# as3320-24BP.net
KiCad netlist of a schematic drawn in EAGLE
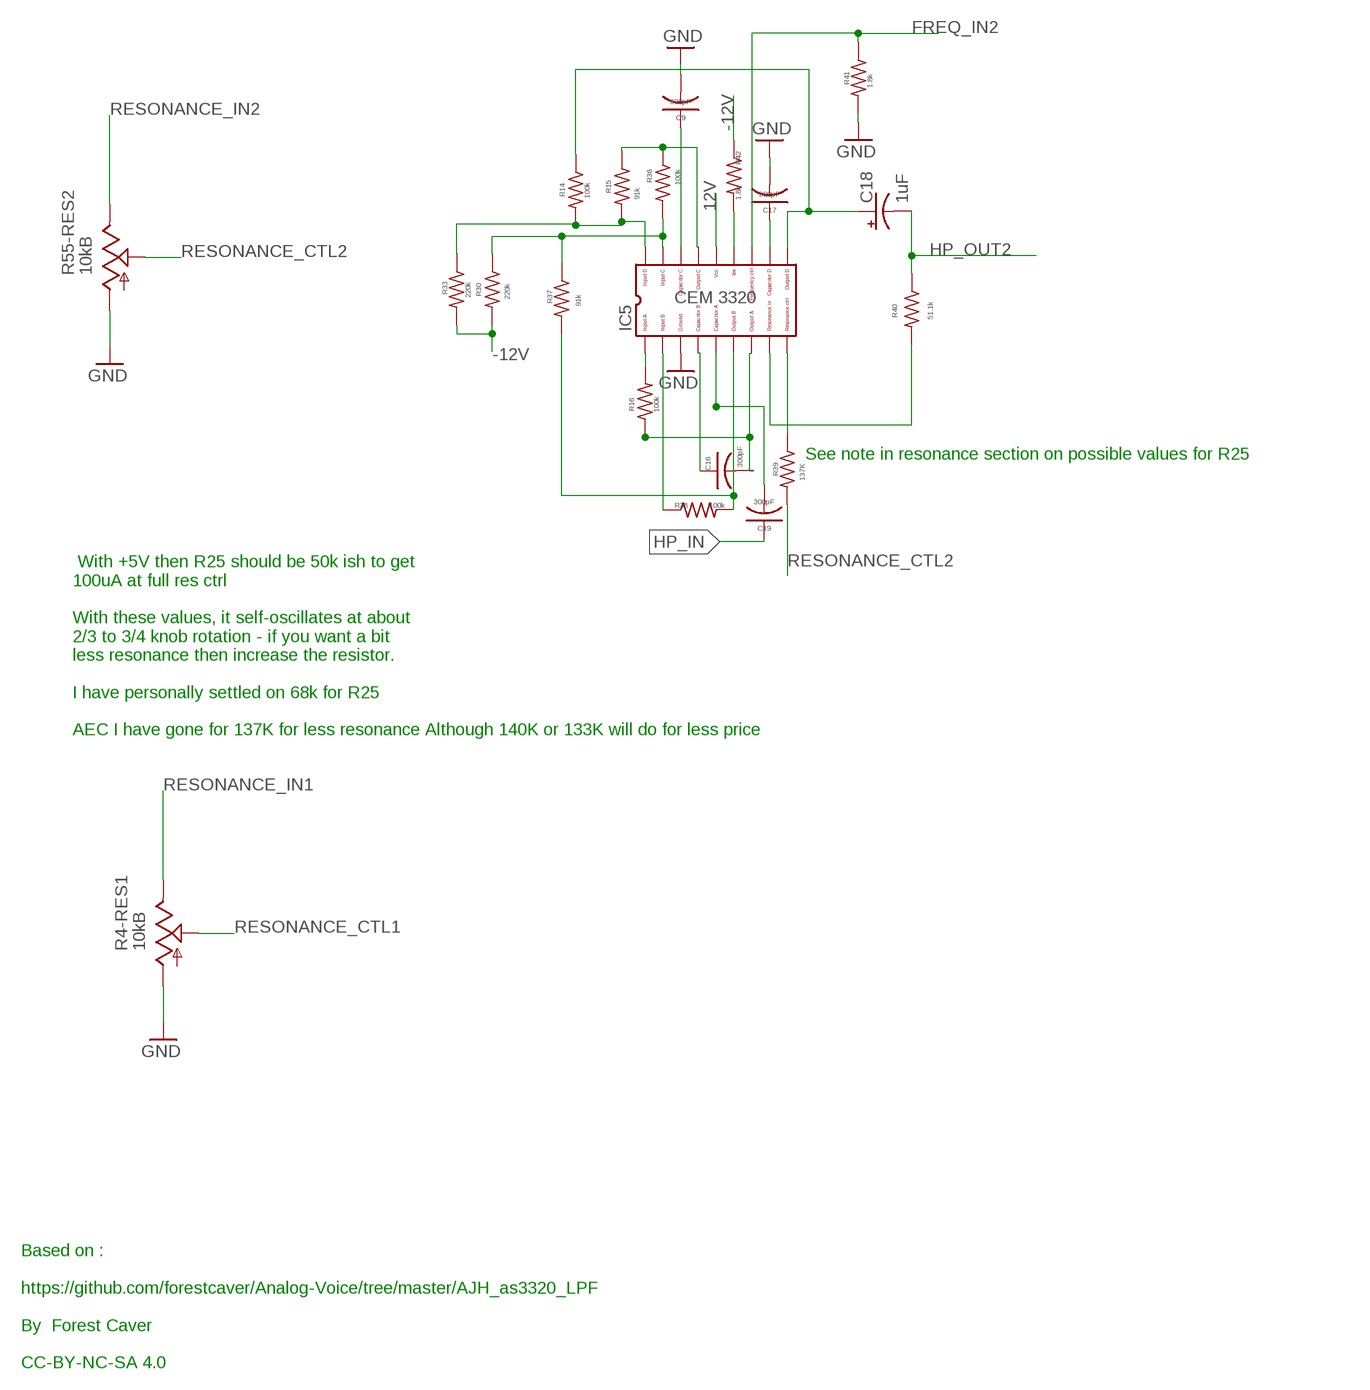
[diagram p0: schematic, sheet 1]
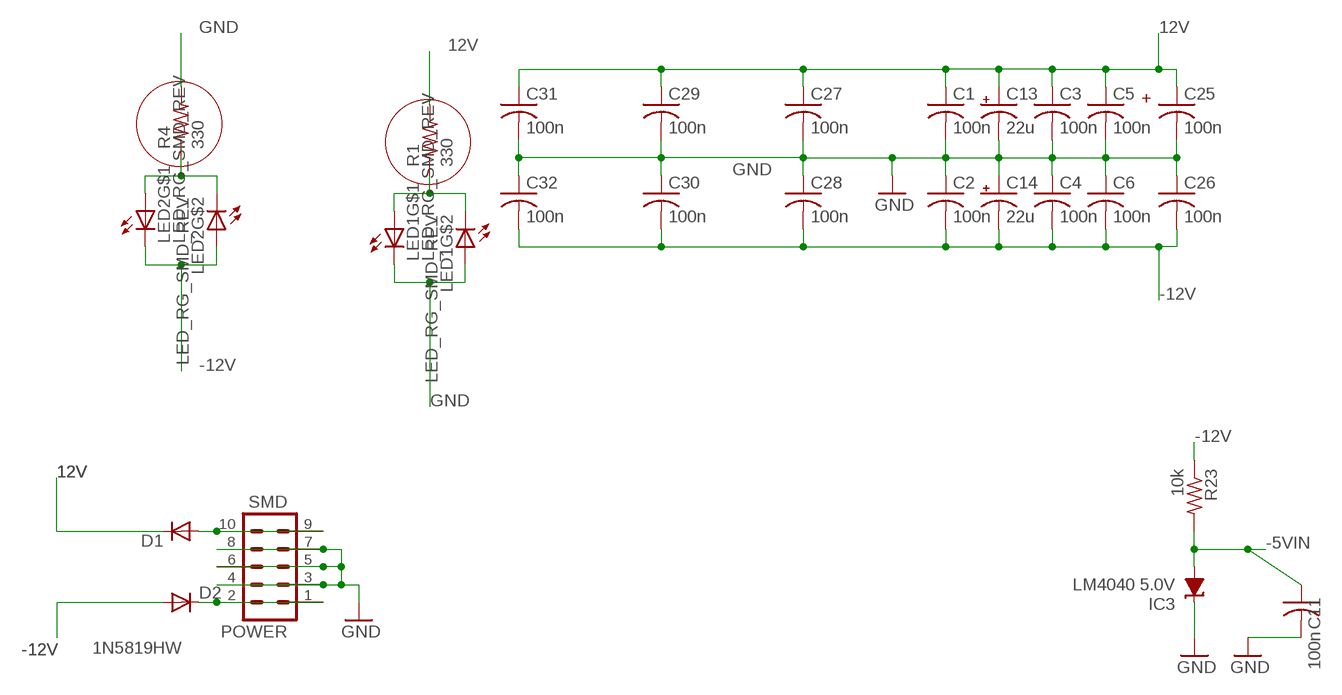
[diagram p1: schematic, sheet 2]
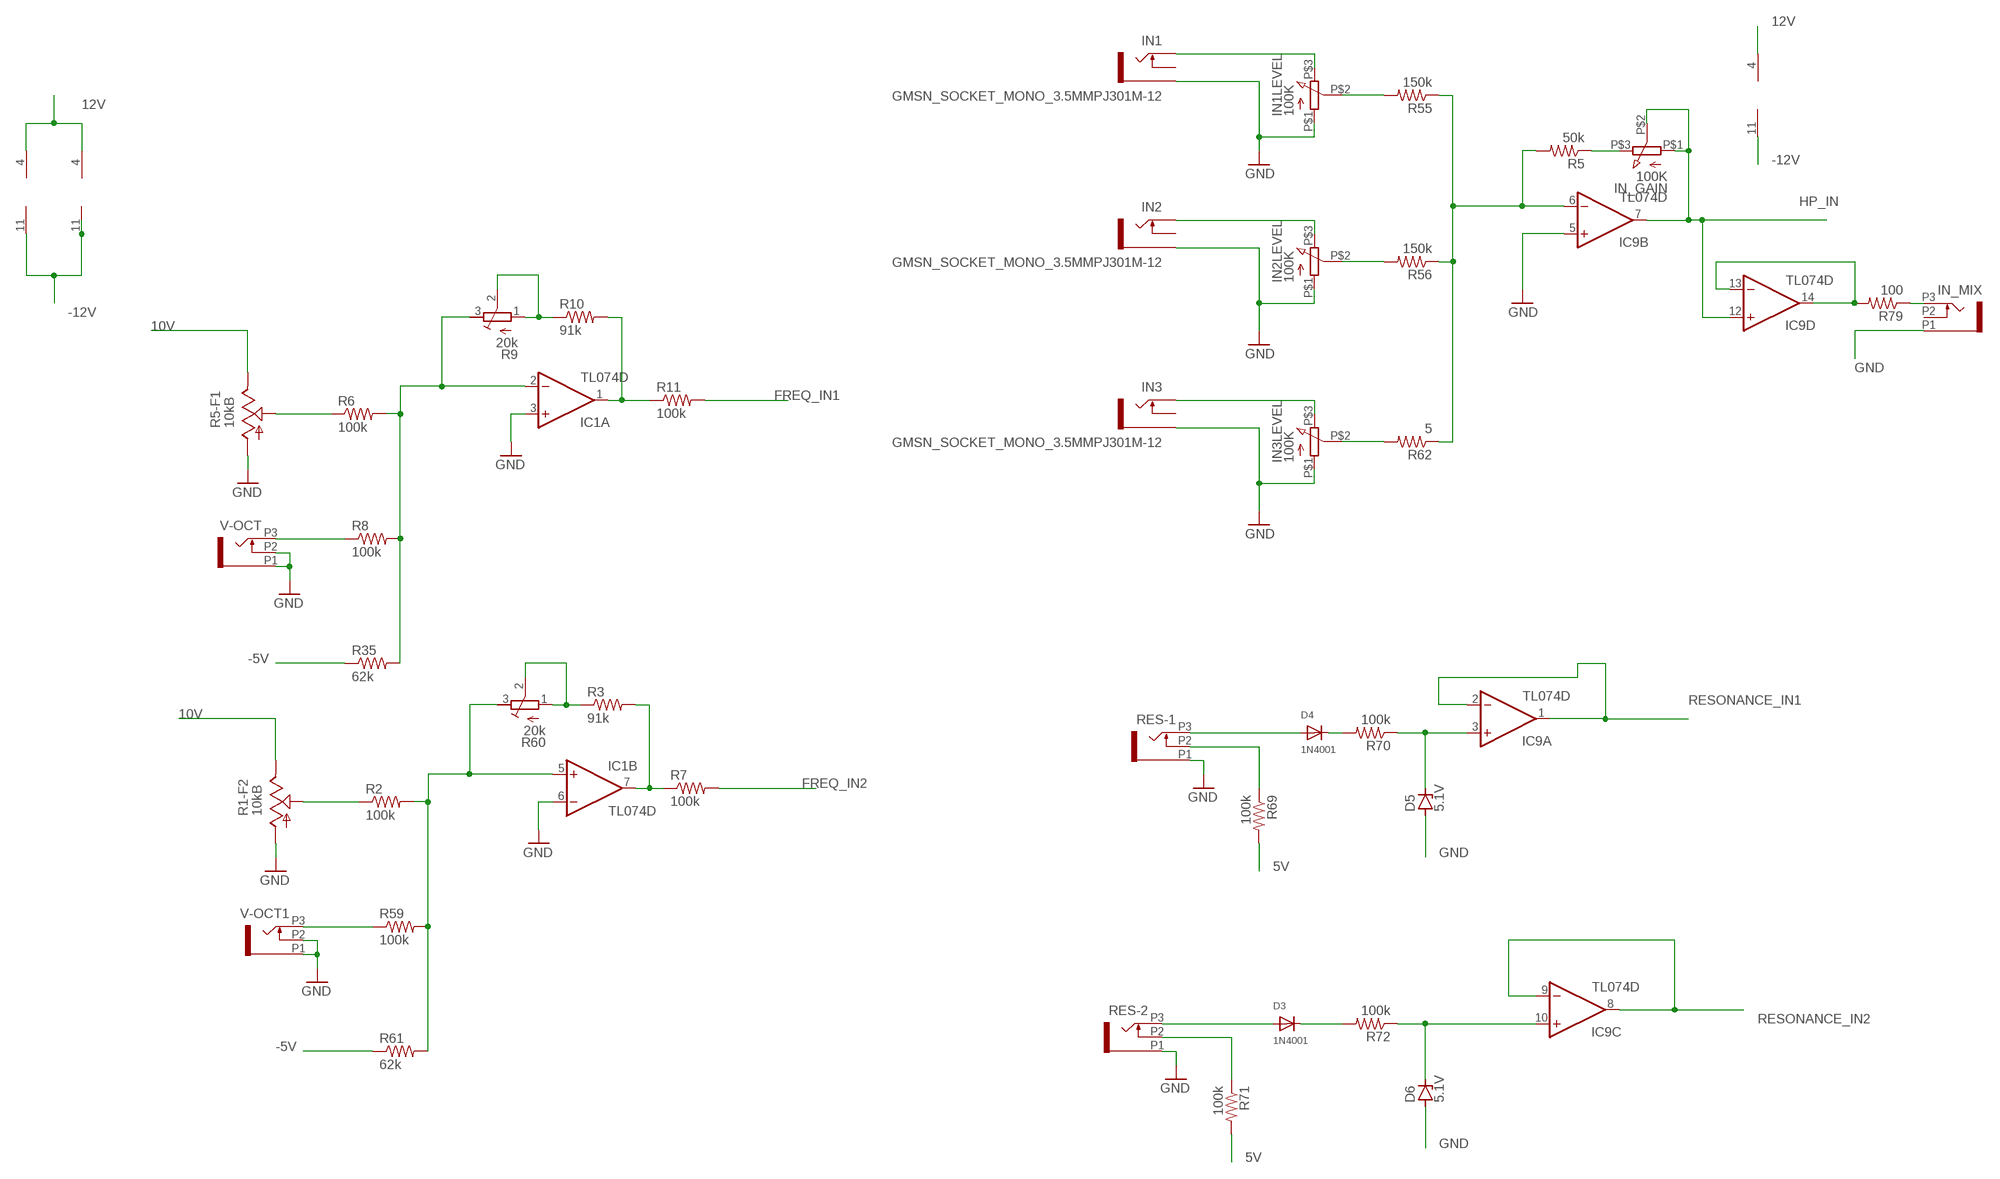
[diagram p2: schematic, sheet 3]
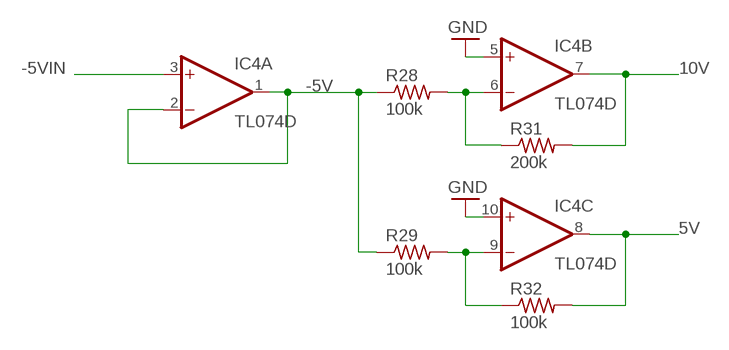
[diagram p3: schematic, sheet 4]
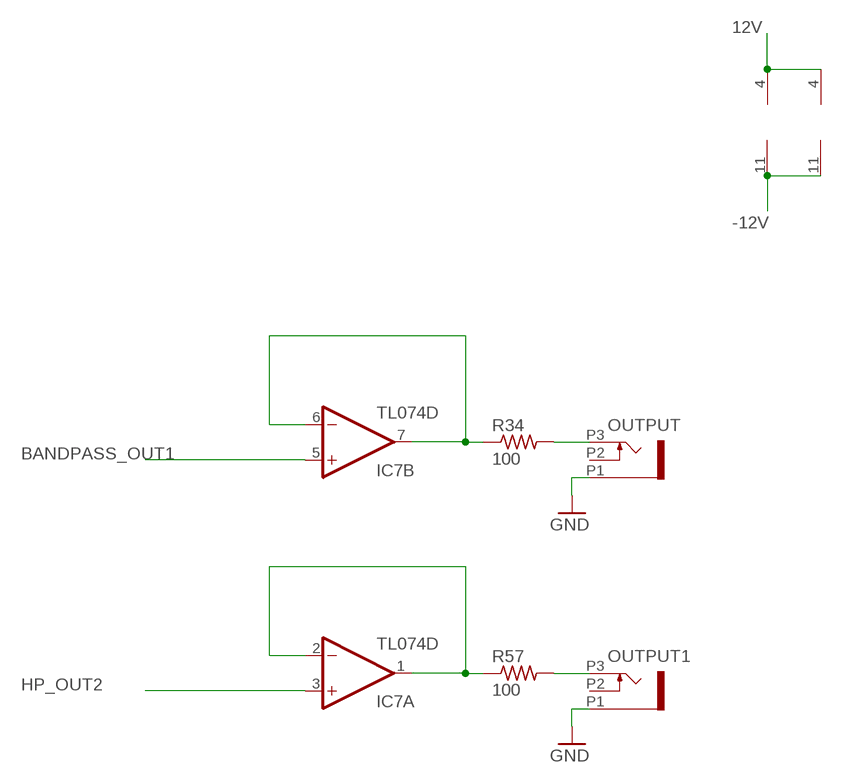
[diagram p4: schematic, sheet 5]

(export (version "E")
  (design (tool "Eeschema 10.0.6"))
  (components
    (comp (ref "D3")
      (value "1N4001")
      (footprint "eagle-import:SMADIODE")
      (libsource (lib "eagle-import") (part "DIODESMA"))
    )
    (comp (ref "D4")
      (value "1N4001")
      (footprint "eagle-import:SMADIODE")
      (libsource (lib "eagle-import") (part "DIODESMA"))
    )
    (comp (ref "D5")
      (value "5.1V")
      (footprint "eagle-import:SOT23")
      (fields (field (name "RS-PART") "816-7962"))
      (libsource (lib "eagle-import") (part "ZENER-DIODESOT23"))
    )
    (comp (ref "D6")
      (value "5.1V")
      (footprint "eagle-import:SOT23")
      (fields (field (name "RS-PART") "816-7962"))
      (libsource (lib "eagle-import") (part "ZENER-DIODESOT23"))
    )
    (comp (ref "IC1")
      (value "TL074D")
      (footprint "eagle-import:SO14")
      (libsource (lib "eagle-import") (part "linear_262_TL074D"))
    )
    (comp (ref "IC4")
      (value "TL074D")
      (footprint "eagle-import:SO14")
      (libsource (lib "eagle-import") (part "linear_262_TL074D"))
    )
    (comp (ref "IC9")
      (value "TL074D")
      (footprint "eagle-import:SO14")
      (libsource (lib "eagle-import") (part "TL074D"))
    )
    (comp (ref "IN1")
      (value "GMSN_SOCKET_MONO_3.5MMPJ301M-12")
      (footprint "eagle-import:GMSN_PJ301M-12")
      (libsource (lib "eagle-import") (part "GMSN_SOCKET_MONO_3.5MMPJ301M-12"))
    )
    (comp (ref "IN1LEVEL")
      (value "100K")
      (footprint "eagle-import:POT")
      (libsource (lib "eagle-import") (part "9MMPOT"))
    )
    (comp (ref "IN2")
      (value "GMSN_SOCKET_MONO_3.5MMPJ301M-12")
      (footprint "eagle-import:GMSN_PJ301M-12")
      (libsource (lib "eagle-import") (part "GMSN_SOCKET_MONO_3.5MMPJ301M-12"))
    )
    (comp (ref "IN2LEVEL")
      (value "100K")
      (footprint "eagle-import:POT")
      (libsource (lib "eagle-import") (part "9MMPOT"))
    )
    (comp (ref "IN3")
      (value "GMSN_SOCKET_MONO_3.5MMPJ301M-12")
      (footprint "eagle-import:GMSN_PJ301M-12")
      (libsource (lib "eagle-import") (part "GMSN_SOCKET_MONO_3.5MMPJ301M-12"))
    )
    (comp (ref "IN3LEVEL")
      (value "100K")
      (footprint "eagle-import:POT")
      (libsource (lib "eagle-import") (part "9MMPOT"))
    )
    (comp (ref "IN_GAIN")
      (value "100K")
      (footprint "eagle-import:POT")
      (libsource (lib "eagle-import") (part "9MMPOT"))
    )
    (comp (ref "IN_MIX")
      (value "PJ301_THONKICONN6")
      (footprint "eagle-import:WQP_PJ_301M6")
      (libsource (lib "eagle-import") (part "PJ301_THONKICONN6"))
    )
    (comp (ref "R1-F2")
      (value "10kB")
      (footprint "eagle-import:ALPS_POT_VERTICAL")
      (libsource (lib "eagle-import") (part "POT_USVERTICAL"))
    )
    (comp (ref "R2")
      (value "100k")
      (footprint "eagle-import:GMSN_M0805")
      (libsource (lib "eagle-import") (part "GMSN_R-US_M0805"))
    )
    (comp (ref "R3")
      (value "91k")
      (footprint "eagle-import:GMSN_M0805")
      (libsource (lib "eagle-import") (part "GMSN_R-US_M0805"))
    )
    (comp (ref "R5")
      (value "50k")
      (footprint "eagle-import:GMSN_M0805")
      (libsource (lib "eagle-import") (part "GMSN_R-US_M0805"))
    )
    (comp (ref "R5-F1")
      (value "10kB")
      (footprint "eagle-import:ALPS_POT_VERTICAL")
      (libsource (lib "eagle-import") (part "POT_USVERTICAL"))
    )
    (comp (ref "R6")
      (value "100k")
      (footprint "eagle-import:GMSN_M0805")
      (libsource (lib "eagle-import") (part "GMSN_R-US_M0805"))
    )
    (comp (ref "R7")
      (value "100k")
      (footprint "eagle-import:GMSN_M0805")
      (libsource (lib "eagle-import") (part "GMSN_R-US_M0805"))
    )
    (comp (ref "R8")
      (value "100k")
      (footprint "eagle-import:GMSN_M0805")
      (libsource (lib "eagle-import") (part "GMSN_R-US_M0805"))
    )
    (comp (ref "R9")
      (value "20k")
      (footprint "eagle-import:RTRIM3296X")
      (libsource (lib "eagle-import") (part "R-TRIMM3296X"))
    )
    (comp (ref "R10")
      (value "91k")
      (footprint "eagle-import:GMSN_M0805")
      (libsource (lib "eagle-import") (part "GMSN_R-US_M0805"))
    )
    (comp (ref "R11")
      (value "100k")
      (footprint "eagle-import:GMSN_M0805")
      (libsource (lib "eagle-import") (part "GMSN_R-US_M0805"))
    )
    (comp (ref "R35")
      (value "62k")
      (footprint "eagle-import:GMSN_M0805")
      (libsource (lib "eagle-import") (part "GMSN_R-US_M0805"))
    )
    (comp (ref "R55")
      (value "150k")
      (footprint "eagle-import:R0805")
      (libsource (lib "eagle-import") (part "GMSN_R-US_R0805"))
    )
    (comp (ref "R56")
      (value "150k")
      (footprint "eagle-import:R0805")
      (libsource (lib "eagle-import") (part "GMSN_R-US_R0805"))
    )
    (comp (ref "R59")
      (value "100k")
      (footprint "eagle-import:GMSN_M0805")
      (libsource (lib "eagle-import") (part "GMSN_R-US_M0805"))
    )
    (comp (ref "R60")
      (value "20k")
      (footprint "eagle-import:RTRIM3296X")
      (libsource (lib "eagle-import") (part "R-TRIMM3296X"))
    )
    (comp (ref "R61")
      (value "62k")
      (footprint "eagle-import:GMSN_M0805")
      (libsource (lib "eagle-import") (part "GMSN_R-US_M0805"))
    )
    (comp (ref "R62")
      (value "5")
      (footprint "eagle-import:R0805")
      (libsource (lib "eagle-import") (part "GMSN_R-US_R0805"))
    )
    (comp (ref "R69")
      (value "100k")
      (footprint "eagle-import:R0805")
      (libsource (lib "eagle-import") (part "GMSN_R-US_R0805"))
    )
    (comp (ref "R70")
      (value "100k")
      (footprint "eagle-import:GMSN_M0805")
      (libsource (lib "eagle-import") (part "GMSN_R-US_M0805"))
    )
    (comp (ref "R71")
      (value "100k")
      (footprint "eagle-import:R0805")
      (libsource (lib "eagle-import") (part "GMSN_R-US_R0805"))
    )
    (comp (ref "R72")
      (value "100k")
      (footprint "eagle-import:GMSN_M0805")
      (libsource (lib "eagle-import") (part "GMSN_R-US_M0805"))
    )
    (comp (ref "R79")
      (value "100")
      (footprint "eagle-import:GMSN_M0805")
      (libsource (lib "eagle-import") (part "GMSN_R-US_M0805"))
    )
    (comp (ref "RES-1")
      (value "PJ301_THONKICONN6")
      (footprint "eagle-import:WQP_PJ_301M6")
      (libsource (lib "eagle-import") (part "PJ301_THONKICONN6"))
    )
    (comp (ref "RES-2")
      (value "PJ301_THONKICONN6")
      (footprint "eagle-import:WQP_PJ_301M6")
      (libsource (lib "eagle-import") (part "PJ301_THONKICONN6"))
    )
    (comp (ref "V-OCT")
      (value "PJ301_THONKICONN6")
      (footprint "eagle-import:WQP_PJ_301M6")
      (libsource (lib "eagle-import") (part "PJ301_THONKICONN6"))
    )
    (comp (ref "V-OCT1")
      (value "PJ301_THONKICONN6")
      (footprint "eagle-import:WQP_PJ_301M6")
      (libsource (lib "eagle-import") (part "PJ301_THONKICONN6"))
    )
    (comp (ref "IC7")
      (value "TL074D")
      (footprint "eagle-import:SO14")
      (libsource (lib "eagle-import") (part "linear_262_TL074D"))
    )
    (comp (ref "IC8")
      (value "TL074D")
      (footprint "eagle-import:SO14")
      (libsource (lib "eagle-import") (part "linear_262_TL074D"))
    )
    (comp (ref "OUTPUT")
      (value "PJ301_THONKICONN6")
      (footprint "eagle-import:WQP_PJ_301M6")
      (libsource (lib "eagle-import") (part "PJ301_THONKICONN6"))
    )
    (comp (ref "OUTPUT1")
      (value "PJ301_THONKICONN6")
      (footprint "eagle-import:WQP_PJ_301M6")
      (libsource (lib "eagle-import") (part "PJ301_THONKICONN6"))
    )
    (comp (ref "R34")
      (value "100")
      (footprint "eagle-import:GMSN_M0805")
      (libsource (lib "eagle-import") (part "GMSN_R-US_M0805"))
    )
    (comp (ref "R57")
      (value "100")
      (footprint "eagle-import:GMSN_M0805")
      (libsource (lib "eagle-import") (part "GMSN_R-US_M0805"))
    )
    (comp (ref "R28")
      (value "100k")
      (footprint "eagle-import:GMSN_M0805")
      (libsource (lib "eagle-import") (part "GMSN_R-US_M0805"))
    )
    (comp (ref "R29")
      (value "100k")
      (footprint "eagle-import:GMSN_M0805")
      (libsource (lib "eagle-import") (part "GMSN_R-US_M0805"))
    )
    (comp (ref "R31")
      (value "200k")
      (footprint "eagle-import:GMSN_M0805")
      (libsource (lib "eagle-import") (part "GMSN_R-US_M0805"))
    )
    (comp (ref "R32")
      (value "100k")
      (footprint "eagle-import:GMSN_M0805")
      (libsource (lib "eagle-import") (part "GMSN_R-US_M0805"))
    )
    (comp (ref "C9")
      (value "300pF")
      (footprint "eagle-import:C0805K")
      (libsource (lib "eagle-import") (part "C-USC0805K"))
    )
    (comp (ref "C16")
      (value "300pF")
      (footprint "eagle-import:C0805K")
      (libsource (lib "eagle-import") (part "C-USC0805K"))
    )
    (comp (ref "C17")
      (value "300pF")
      (footprint "eagle-import:C0805K")
      (libsource (lib "eagle-import") (part "C-USC0805K"))
    )
    (comp (ref "C18")
      (value "1uF")
      (footprint "eagle-import:PANASONIC_B")
      (libsource (lib "eagle-import") (part "rcl_334_CPOL-USB"))
    )
    (comp (ref "C19")
      (value "300pF")
      (footprint "eagle-import:C0805K")
      (libsource (lib "eagle-import") (part "C-USC0805K"))
    )
    (comp (ref "IC5")
      (value "CEM3320")
      (footprint "eagle-import:DIL18")
      (libsource (lib "eagle-import") (part "CEM3320"))
    )
    (comp (ref "R4-RES1")
      (value "10kB")
      (footprint "eagle-import:ALPS_POT_VERTICAL")
      (libsource (lib "eagle-import") (part "POT_USVERTICAL"))
    )
    (comp (ref "R14")
      (value "100k")
      (footprint "eagle-import:GMSN_M0805")
      (libsource (lib "eagle-import") (part "GMSN_R-US_M0805"))
    )
    (comp (ref "R15")
      (value "91k")
      (footprint "eagle-import:GMSN_M0805")
      (libsource (lib "eagle-import") (part "GMSN_R-US_M0805"))
    )
    (comp (ref "R16")
      (value "100k")
      (footprint "eagle-import:GMSN_M0805")
      (libsource (lib "eagle-import") (part "GMSN_R-US_M0805"))
    )
    (comp (ref "R30")
      (value "220k")
      (footprint "eagle-import:GMSN_M0805")
      (libsource (lib "eagle-import") (part "GMSN_R-US_M0805"))
    )
    (comp (ref "R33")
      (value "220k")
      (footprint "eagle-import:GMSN_M0805")
      (libsource (lib "eagle-import") (part "GMSN_R-US_M0805"))
    )
    (comp (ref "R36")
      (value "100k")
      (footprint "eagle-import:GMSN_M0805")
      (libsource (lib "eagle-import") (part "GMSN_R-US_M0805"))
    )
    (comp (ref "R37")
      (value "91k")
      (footprint "eagle-import:GMSN_M0805")
      (libsource (lib "eagle-import") (part "GMSN_R-US_M0805"))
    )
    (comp (ref "R38")
      (value "100k")
      (footprint "eagle-import:GMSN_M0805")
      (libsource (lib "eagle-import") (part "GMSN_R-US_M0805"))
    )
    (comp (ref "R39")
      (value "137K")
      (footprint "eagle-import:GMSN_M0805")
      (libsource (lib "eagle-import") (part "GMSN_R-US_M0805"))
    )
    (comp (ref "R40")
      (value "51.1k")
      (footprint "eagle-import:GMSN_M0805")
      (libsource (lib "eagle-import") (part "GMSN_R-US_M0805"))
    )
    (comp (ref "R41")
      (value "1.8k")
      (footprint "eagle-import:GMSN_M0805")
      (libsource (lib "eagle-import") (part "GMSN_R-US_M0805"))
    )
    (comp (ref "R42")
      (value "1.8k")
      (footprint "eagle-import:GMSN_M0805")
      (libsource (lib "eagle-import") (part "GMSN_R-US_M0805"))
    )
    (comp (ref "R55-RES2")
      (value "10kB")
      (footprint "eagle-import:ALPS_POT_VERTICAL")
      (libsource (lib "eagle-import") (part "POT_USVERTICAL"))
    )
    (comp (ref "C1")
      (value "100n")
      (footprint "eagle-import:C0805K")
      (libsource (lib "eagle-import") (part "C-USC0805K"))
    )
    (comp (ref "C2")
      (value "100n")
      (footprint "eagle-import:C0805K")
      (libsource (lib "eagle-import") (part "C-USC0805K"))
    )
    (comp (ref "C3")
      (value "100n")
      (footprint "eagle-import:C0805K")
      (libsource (lib "eagle-import") (part "C-USC0805K"))
    )
    (comp (ref "C4")
      (value "100n")
      (footprint "eagle-import:C0805K")
      (libsource (lib "eagle-import") (part "C-USC0805K"))
    )
    (comp (ref "C5")
      (value "100n")
      (footprint "eagle-import:C0805K")
      (libsource (lib "eagle-import") (part "C-USC0805K"))
    )
    (comp (ref "C6")
      (value "100n")
      (footprint "eagle-import:C0805K")
      (libsource (lib "eagle-import") (part "C-USC0805K"))
    )
    (comp (ref "C11")
      (value "100n")
      (footprint "eagle-import:GMSN_C0805K")
      (libsource (lib "eagle-import") (part "GMSN_C-USC0805K"))
    )
    (comp (ref "C13")
      (value "22u")
      (footprint "eagle-import:PANASONIC_B")
      (libsource (lib "eagle-import") (part "CPOL-USB"))
    )
    (comp (ref "C14")
      (value "22u")
      (footprint "eagle-import:PANASONIC_B")
      (libsource (lib "eagle-import") (part "CPOL-USB"))
    )
    (comp (ref "C25")
      (value "100n")
      (footprint "eagle-import:C0805K")
      (libsource (lib "eagle-import") (part "C-USC0805K"))
    )
    (comp (ref "C26")
      (value "100n")
      (footprint "eagle-import:C0805K")
      (libsource (lib "eagle-import") (part "C-USC0805K"))
    )
    (comp (ref "C27")
      (value "100n")
      (footprint "eagle-import:C0805K")
      (libsource (lib "eagle-import") (part "C-USC0805K"))
    )
    (comp (ref "C28")
      (value "100n")
      (footprint "eagle-import:C0805K")
      (libsource (lib "eagle-import") (part "C-USC0805K"))
    )
    (comp (ref "C29")
      (value "100n")
      (footprint "eagle-import:C0805K")
      (libsource (lib "eagle-import") (part "C-USC0805K"))
    )
    (comp (ref "C30")
      (value "100n")
      (footprint "eagle-import:C0805K")
      (libsource (lib "eagle-import") (part "C-USC0805K"))
    )
    (comp (ref "C31")
      (value "100n")
      (footprint "eagle-import:C0805K")
      (libsource (lib "eagle-import") (part "C-USC0805K"))
    )
    (comp (ref "C32")
      (value "100n")
      (footprint "eagle-import:C0805K")
      (libsource (lib "eagle-import") (part "C-USC0805K"))
    )
    (comp (ref "D1")
      (value "1N5819HW")
      (footprint "eagle-import:SOD123")
      (libsource (lib "eagle-import") (part "DIODE-SOD123"))
    )
    (comp (ref "D2")
      (value "1N5819HW")
      (footprint "eagle-import:SOD123")
      (libsource (lib "eagle-import") (part "DIODE-SOD123"))
    )
    (comp (ref "IC3")
      (value "LM4040 5.0V")
      (footprint "eagle-import:DBZ_R-PDSO-G3")
      (libsource (lib "eagle-import") (part "LM4041DBZC12"))
    )
    (comp (ref "LED1")
      (value "LED_RG_SMD_REV")
      (footprint "eagle-import:LSG_T77K")
      (fields (field (name "RS-PART") "915-4828"))
      (libsource (lib "eagle-import") (part "LED_RG_SMD_REV"))
    )
    (comp (ref "LED2")
      (value "LED_RG_SMD_REV")
      (footprint "eagle-import:LSG_T77K")
      (libsource (lib "eagle-import") (part "LED_RG_SMD_REV"))
    )
    (comp (ref "POWER")
      (value "SMD")
      (footprint "eagle-import:2X5-SHROUDED_SMD")
      (fields (field (name "RS-PART") "828-1783"))
      (libsource (lib "eagle-import") (part "CONN_05X2SHD_SMD"))
    )
    (comp (ref "R1")
      (value "330")
      (footprint "eagle-import:GMSN_M0805")
      (libsource (lib "eagle-import") (part "GMSN_R-US_M0805"))
    )
    (comp (ref "R4")
      (value "330")
      (footprint "eagle-import:GMSN_M0805")
      (fields (field (name "RS-PART") "915-4828"))
      (libsource (lib "eagle-import") (part "GMSN_R-US_M0805"))
    )
    (comp (ref "R23")
      (value "10k")
      (footprint "eagle-import:GMSN_M0805")
      (libsource (lib "eagle-import") (part "GMSN_R-US_M0805"))
    )
  )
  (nets
    (net (code "1") (name "-5V") (class "Default")
      (node (ref "IC4") (pin "1") (pinfunction "OUT_1") (pintype "output"))
      (node (ref "IC4") (pin "2") (pinfunction "-IN_2") (pintype "input"))
      (node (ref "R28") (pin "1") (pinfunction "1_1") (pintype "passive"))
      (node (ref "R29") (pin "1") (pinfunction "1_1") (pintype "passive"))
      (node (ref "R35") (pin "1") (pinfunction "1_1") (pintype "passive"))
      (node (ref "R61") (pin "1") (pinfunction "1_1") (pintype "passive"))
    )
    (net (code "2") (name "-5VIN") (class "Default")
      (node (ref "C11") (pin "1") (pinfunction "1_1") (pintype "passive"))
      (node (ref "IC3") (pin "2") (pinfunction "A_2") (pintype "passive"))
      (node (ref "IC4") (pin "3") (pinfunction "+IN_3") (pintype "input"))
      (node (ref "R23") (pin "2") (pinfunction "2_2") (pintype "passive"))
    )
    (net (code "3") (name "-12V") (class "Default")
      (node (ref "C14") (pin "-") (pinfunction "-_-") (pintype "passive"))
      (node (ref "C2") (pin "2") (pinfunction "2_2") (pintype "passive"))
      (node (ref "C26") (pin "2") (pinfunction "2_2") (pintype "passive"))
      (node (ref "C28") (pin "2") (pinfunction "2_2") (pintype "passive"))
      (node (ref "C30") (pin "2") (pinfunction "2_2") (pintype "passive"))
      (node (ref "C32") (pin "2") (pinfunction "2_2") (pintype "passive"))
      (node (ref "C4") (pin "2") (pinfunction "2_2") (pintype "passive"))
      (node (ref "C6") (pin "2") (pinfunction "2_2") (pintype "passive"))
      (node (ref "D2") (pin "A") (pinfunction "A_A") (pintype "passive"))
      (node (ref "IC1") (pin "11") (pinfunction "V-_11") (pintype "power_in"))
      (node (ref "IC4") (pin "11") (pinfunction "V-_11") (pintype "power_in"))
      (node (ref "IC7") (pin "11") (pinfunction "V-_11") (pintype "power_in"))
      (node (ref "IC8") (pin "11") (pinfunction "V-_11") (pintype "power_in"))
      (node (ref "IC9") (pin "11") (pinfunction "V-_11") (pintype "power_in"))
      (node (ref "LED2") (pin "1") (pinfunction "C_1") (pintype "passive"))
      (node (ref "LED2") (pin "4") (pinfunction "A_4") (pintype "passive"))
      (node (ref "R23") (pin "1") (pinfunction "1_1") (pintype "passive"))
      (node (ref "R30") (pin "2") (pinfunction "2_2") (pintype "passive"))
      (node (ref "R33") (pin "2") (pinfunction "2_2") (pintype "passive"))
      (node (ref "R42") (pin "1") (pinfunction "1_1") (pintype "passive"))
    )
    (net (code "4") (name "5V") (class "Default")
      (node (ref "IC4") (pin "8") (pinfunction "OUT_8") (pintype "output"))
      (node (ref "R32") (pin "2") (pinfunction "2_2") (pintype "passive"))
      (node (ref "R69") (pin "2") (pinfunction "2_2") (pintype "passive"))
      (node (ref "R71") (pin "2") (pinfunction "2_2") (pintype "passive"))
    )
    (net (code "5") (name "10V") (class "Default")
      (node (ref "IC4") (pin "7") (pinfunction "OUT_7") (pintype "output"))
      (node (ref "R1-F2") (pin "P$1") (pinfunction "E_P$1") (pintype "passive"))
      (node (ref "R31") (pin "2") (pinfunction "2_2") (pintype "passive"))
      (node (ref "R5-F1") (pin "P$1") (pinfunction "E_P$1") (pintype "passive"))
    )
    (net (code "6") (name "12V") (class "Default")
      (node (ref "C1") (pin "1") (pinfunction "1_1") (pintype "passive"))
      (node (ref "C13") (pin "+") (pinfunction "+_+") (pintype "passive"))
      (node (ref "C25") (pin "1") (pinfunction "1_1") (pintype "passive"))
      (node (ref "C27") (pin "1") (pinfunction "1_1") (pintype "passive"))
      (node (ref "C29") (pin "1") (pinfunction "1_1") (pintype "passive"))
      (node (ref "C3") (pin "1") (pinfunction "1_1") (pintype "passive"))
      (node (ref "C31") (pin "1") (pinfunction "1_1") (pintype "passive"))
      (node (ref "C5") (pin "1") (pinfunction "1_1") (pintype "passive"))
      (node (ref "D1") (pin "C") (pinfunction "C_C") (pintype "passive"))
      (node (ref "IC1") (pin "4") (pinfunction "V+_4") (pintype "power_in"))
      (node (ref "IC4") (pin "4") (pinfunction "V+_4") (pintype "power_in"))
      (node (ref "IC5") (pin "14") (pinfunction "14_14") (pintype "power_in"))
      (node (ref "IC7") (pin "4") (pinfunction "V+_4") (pintype "power_in"))
      (node (ref "IC8") (pin "4") (pinfunction "V+_4") (pintype "power_in"))
      (node (ref "IC9") (pin "4") (pinfunction "V+_4") (pintype "power_in"))
      (node (ref "R1") (pin "2") (pinfunction "2_2") (pintype "passive"))
    )
    (net (code "7") (name "BANDPASS_OUT1") (class "Default")
      (node (ref "IC7") (pin "5") (pinfunction "+IN_5") (pintype "input"))
    )
    (net (code "8") (name "FREQ_IN1") (class "Default")
      (node (ref "R11") (pin "2") (pinfunction "2_2") (pintype "passive"))
    )
    (net (code "9") (name "FREQ_IN2") (class "Default")
      (node (ref "IC5") (pin "12") (pinfunction "12_12") (pintype "bidirectional"))
      (node (ref "R41") (pin "1") (pinfunction "1_1") (pintype "passive"))
      (node (ref "R7") (pin "2") (pinfunction "2_2") (pintype "passive"))
    )
    (net (code "10") (name "GND") (class "Default")
      (node (ref "C1") (pin "2") (pinfunction "2_2") (pintype "passive"))
      (node (ref "C11") (pin "2") (pinfunction "2_2") (pintype "passive"))
      (node (ref "C13") (pin "-") (pinfunction "-_-") (pintype "passive"))
      (node (ref "C14") (pin "+") (pinfunction "+_+") (pintype "passive"))
      (node (ref "C17") (pin "2") (pinfunction "2_2") (pintype "passive"))
      (node (ref "C2") (pin "1") (pinfunction "1_1") (pintype "passive"))
      (node (ref "C25") (pin "2") (pinfunction "2_2") (pintype "passive"))
      (node (ref "C26") (pin "1") (pinfunction "1_1") (pintype "passive"))
      (node (ref "C27") (pin "2") (pinfunction "2_2") (pintype "passive"))
      (node (ref "C28") (pin "1") (pinfunction "1_1") (pintype "passive"))
      (node (ref "C29") (pin "2") (pinfunction "2_2") (pintype "passive"))
      (node (ref "C3") (pin "2") (pinfunction "2_2") (pintype "passive"))
      (node (ref "C30") (pin "1") (pinfunction "1_1") (pintype "passive"))
      (node (ref "C31") (pin "2") (pinfunction "2_2") (pintype "passive"))
      (node (ref "C32") (pin "1") (pinfunction "1_1") (pintype "passive"))
      (node (ref "C4") (pin "1") (pinfunction "1_1") (pintype "passive"))
      (node (ref "C5") (pin "2") (pinfunction "2_2") (pintype "passive"))
      (node (ref "C6") (pin "1") (pinfunction "1_1") (pintype "passive"))
      (node (ref "C9") (pin "2") (pinfunction "2_2") (pintype "passive"))
      (node (ref "D5") (pin "1") (pinfunction "A_1") (pintype "passive"))
      (node (ref "D6") (pin "1") (pinfunction "A_1") (pintype "passive"))
      (node (ref "IC1") (pin "3") (pinfunction "+IN_3") (pintype "input"))
      (node (ref "IC1") (pin "6") (pinfunction "-IN_6") (pintype "input"))
      (node (ref "IC3") (pin "1") (pinfunction "C_1") (pintype "passive"))
      (node (ref "IC4") (pin "10") (pinfunction "+IN_10") (pintype "input"))
      (node (ref "IC4") (pin "5") (pinfunction "+IN_5") (pintype "input"))
      (node (ref "IC5") (pin "3") (pinfunction "3_3") (pintype "power_in"))
      (node (ref "IC9") (pin "5") (pinfunction "+IN_5") (pintype "input"))
      (node (ref "IN1") (pin "GND") (pinfunction "SLEEVE_GND") (pintype "passive"))
      (node (ref "IN1LEVEL") (pin "P$1") (pinfunction "1_P$1") (pintype "passive"))
      (node (ref "IN2") (pin "GND") (pinfunction "SLEEVE_GND") (pintype "passive"))
      (node (ref "IN2LEVEL") (pin "P$1") (pinfunction "1_P$1") (pintype "passive"))
      (node (ref "IN3") (pin "GND") (pinfunction "SLEEVE_GND") (pintype "passive"))
      (node (ref "IN3LEVEL") (pin "P$1") (pinfunction "1_P$1") (pintype "passive"))
      (node (ref "IN_MIX") (pin "P1") (pinfunction "1_P1") (pintype "passive"))
      (node (ref "LED1") (pin "1") (pinfunction "C_1") (pintype "passive"))
      (node (ref "LED1") (pin "4") (pinfunction "A_4") (pintype "passive"))
      (node (ref "OUTPUT") (pin "P1") (pinfunction "1_P1") (pintype "passive"))
      (node (ref "OUTPUT1") (pin "P1") (pinfunction "1_P1") (pintype "passive"))
      (node (ref "POWER") (pin "3") (pinfunction "3_3") (pintype "passive"))
      (node (ref "POWER") (pin "4") (pinfunction "4_4") (pintype "passive"))
      (node (ref "POWER") (pin "5") (pinfunction "5_5") (pintype "passive"))
      (node (ref "POWER") (pin "6") (pinfunction "6_6") (pintype "passive"))
      (node (ref "POWER") (pin "7") (pinfunction "7_7") (pintype "passive"))
      (node (ref "POWER") (pin "8") (pinfunction "8_8") (pintype "passive"))
      (node (ref "R1-F2") (pin "P$3") (pinfunction "A_P$3") (pintype "passive"))
      (node (ref "R4") (pin "2") (pinfunction "2_2") (pintype "passive"))
      (node (ref "R4-RES1") (pin "P$3") (pinfunction "A_P$3") (pintype "passive"))
      (node (ref "R41") (pin "2") (pinfunction "2_2") (pintype "passive"))
      (node (ref "R5-F1") (pin "P$3") (pinfunction "A_P$3") (pintype "passive"))
      (node (ref "R55-RES2") (pin "P$3") (pinfunction "A_P$3") (pintype "passive"))
      (node (ref "RES-1") (pin "P1") (pinfunction "1_P1") (pintype "passive"))
      (node (ref "RES-2") (pin "P1") (pinfunction "1_P1") (pintype "passive"))
      (node (ref "V-OCT") (pin "P1") (pinfunction "1_P1") (pintype "passive"))
      (node (ref "V-OCT") (pin "P2") (pinfunction "2_P2") (pintype "passive"))
      (node (ref "V-OCT1") (pin "P1") (pinfunction "1_P1") (pintype "passive"))
      (node (ref "V-OCT1") (pin "P2") (pinfunction "2_P2") (pintype "passive"))
    )
    (net (code "11") (name "HP_IN") (class "Default")
      (node (ref "C19") (pin "1") (pinfunction "1_1") (pintype "passive"))
      (node (ref "IC9") (pin "12") (pinfunction "+IN_12") (pintype "input"))
      (node (ref "IC9") (pin "7") (pinfunction "OUT_7") (pintype "output"))
      (node (ref "IN_GAIN") (pin "P$1") (pinfunction "1_P$1") (pintype "passive"))
      (node (ref "IN_GAIN") (pin "P$2") (pinfunction "2_P$2") (pintype "passive"))
    )
    (net (code "12") (name "HP_OUT2") (class "Default")
      (node (ref "C18") (pin "-") (pinfunction "-_-") (pintype "passive"))
      (node (ref "IC7") (pin "3") (pinfunction "+IN_3") (pintype "input"))
      (node (ref "R40") (pin "1") (pinfunction "1_1") (pintype "passive"))
    )
    (net (code "13") (name "Net-(C9-Pad1)") (class "Default")
      (node (ref "C9") (pin "1") (pinfunction "1_1") (pintype "passive"))
      (node (ref "IC5") (pin "16") (pinfunction "16_16") (pintype "bidirectional"))
    )
    (net (code "14") (name "Net-(C16-Pad1)") (class "Default")
      (node (ref "C16") (pin "1") (pinfunction "1_1") (pintype "passive"))
      (node (ref "IC5") (pin "4") (pinfunction "4_4") (pintype "bidirectional"))
    )
    (net (code "15") (name "Net-(C16-Pad2)") (class "Default")
      (node (ref "C16") (pin "2") (pinfunction "2_2") (pintype "passive"))
      (node (ref "IC5") (pin "7") (pinfunction "7_7") (pintype "output"))
      (node (ref "R16") (pin "1") (pinfunction "1_1") (pintype "passive"))
    )
    (net (code "16") (name "Net-(C17-Pad1)") (class "Default")
      (node (ref "C17") (pin "1") (pinfunction "1_1") (pintype "passive"))
      (node (ref "IC5") (pin "11") (pinfunction "11_11") (pintype "output"))
    )
    (net (code "17") (name "Net-(C18-Pad+)") (class "Default")
      (node (ref "C18") (pin "+") (pinfunction "+_+") (pintype "passive"))
      (node (ref "IC5") (pin "10") (pinfunction "10_10") (pintype "output"))
      (node (ref "R14") (pin "1") (pinfunction "1_1") (pintype "passive"))
    )
    (net (code "18") (name "Net-(C19-Pad2)") (class "Default")
      (node (ref "C19") (pin "2") (pinfunction "2_2") (pintype "passive"))
      (node (ref "IC5") (pin "5") (pinfunction "5_5") (pintype "bidirectional"))
    )
    (net (code "19") (name "Net-(D1-PadA)") (class "Default")
      (node (ref "D1") (pin "A") (pinfunction "A_A") (pintype "passive"))
      (node (ref "POWER") (pin "10") (pinfunction "10_10") (pintype "passive"))
      (node (ref "POWER") (pin "9") (pinfunction "9_9") (pintype "passive"))
    )
    (net (code "20") (name "Net-(D2-PadC)") (class "Default")
      (node (ref "D2") (pin "C") (pinfunction "C_C") (pintype "passive"))
      (node (ref "POWER") (pin "1") (pinfunction "1_1") (pintype "passive"))
      (node (ref "POWER") (pin "2") (pinfunction "2_2") (pintype "passive"))
    )
    (net (code "21") (name "Net-(D3-PadC)") (class "Default")
      (node (ref "D3") (pin "C") (pinfunction "C_C") (pintype "passive"))
      (node (ref "R72") (pin "2") (pinfunction "2_2") (pintype "passive"))
    )
    (net (code "22") (name "Net-(D4-PadC)") (class "Default")
      (node (ref "D4") (pin "C") (pinfunction "C_C") (pintype "passive"))
      (node (ref "R70") (pin "2") (pinfunction "2_2") (pintype "passive"))
    )
    (net (code "23") (name "Net-(D5-C)") (class "Default")
      (node (ref "D5") (pin "3") (pinfunction "C_3") (pintype "passive"))
      (node (ref "IC9") (pin "3") (pinfunction "+IN_3") (pintype "input"))
      (node (ref "R70") (pin "1") (pinfunction "1_1") (pintype "passive"))
    )
    (net (code "24") (name "Net-(D6-C)") (class "Default")
      (node (ref "D6") (pin "3") (pinfunction "C_3") (pintype "passive"))
      (node (ref "IC9") (pin "10") (pinfunction "+IN_10") (pintype "input"))
      (node (ref "R72") (pin "1") (pinfunction "1_1") (pintype "passive"))
    )
    (net (code "25") (name "Net-(IC1A--IN)") (class "Default")
      (node (ref "IC1") (pin "2") (pinfunction "-IN_2") (pintype "input"))
      (node (ref "R35") (pin "2") (pinfunction "2_2") (pintype "passive"))
      (node (ref "R6") (pin "2") (pinfunction "2_2") (pintype "passive"))
      (node (ref "R8") (pin "2") (pinfunction "2_2") (pintype "passive"))
      (node (ref "R9") (pin "3") (pinfunction "A_3") (pintype "passive"))
    )
    (net (code "26") (name "Net-(IC1A-OUT)") (class "Default")
      (node (ref "IC1") (pin "1") (pinfunction "OUT_1") (pintype "output"))
      (node (ref "R10") (pin "2") (pinfunction "2_2") (pintype "passive"))
      (node (ref "R11") (pin "1") (pinfunction "1_1") (pintype "passive"))
    )
    (net (code "27") (name "Net-(IC1B-+IN)") (class "Default")
      (node (ref "IC1") (pin "5") (pinfunction "+IN_5") (pintype "input"))
      (node (ref "R2") (pin "2") (pinfunction "2_2") (pintype "passive"))
      (node (ref "R59") (pin "2") (pinfunction "2_2") (pintype "passive"))
      (node (ref "R60") (pin "3") (pinfunction "A_3") (pintype "passive"))
      (node (ref "R61") (pin "2") (pinfunction "2_2") (pintype "passive"))
    )
    (net (code "28") (name "Net-(IC1B-OUT)") (class "Default")
      (node (ref "IC1") (pin "7") (pinfunction "OUT_7") (pintype "output"))
      (node (ref "R3") (pin "2") (pinfunction "2_2") (pintype "passive"))
      (node (ref "R7") (pin "1") (pinfunction "1_1") (pintype "passive"))
    )
    (net (code "29") (name "Net-(IC4B--IN)") (class "Default")
      (node (ref "IC4") (pin "6") (pinfunction "-IN_6") (pintype "input"))
      (node (ref "R28") (pin "2") (pinfunction "2_2") (pintype "passive"))
      (node (ref "R31") (pin "1") (pinfunction "1_1") (pintype "passive"))
    )
    (net (code "30") (name "Net-(IC4C--IN)") (class "Default")
      (node (ref "IC4") (pin "9") (pinfunction "-IN_9") (pintype "input"))
      (node (ref "R29") (pin "2") (pinfunction "2_2") (pintype "passive"))
      (node (ref "R32") (pin "1") (pinfunction "1_1") (pintype "passive"))
    )
    (net (code "31") (name "Net-(IC5-Pad1)") (class "Default")
      (node (ref "IC5") (pin "1") (pinfunction "1_1") (pintype "input"))
      (node (ref "R16") (pin "2") (pinfunction "2_2") (pintype "passive"))
    )
    (net (code "32") (name "Net-(IC5-Pad2)") (class "Default")
      (node (ref "IC5") (pin "2") (pinfunction "2_2") (pintype "input"))
      (node (ref "R38") (pin "1") (pinfunction "1_1") (pintype "passive"))
    )
    (net (code "33") (name "Net-(IC5-Pad6)") (class "Default")
      (node (ref "IC5") (pin "6") (pinfunction "6_6") (pintype "output"))
      (node (ref "R37") (pin "2") (pinfunction "2_2") (pintype "passive"))
      (node (ref "R38") (pin "2") (pinfunction "2_2") (pintype "passive"))
    )
    (net (code "34") (name "Net-(IC5-Pad8)") (class "Default")
      (node (ref "IC5") (pin "8") (pinfunction "8_8") (pintype "input"))
      (node (ref "R40") (pin "2") (pinfunction "2_2") (pintype "passive"))
    )
    (net (code "35") (name "Net-(IC5-Pad9)") (class "Default")
      (node (ref "IC5") (pin "9") (pinfunction "9_9") (pintype "input"))
      (node (ref "R39") (pin "1") (pinfunction "1_1") (pintype "passive"))
    )
    (net (code "36") (name "Net-(IC5-Pad13)") (class "Default")
      (node (ref "IC5") (pin "13") (pinfunction "13_13") (pintype "power_in"))
      (node (ref "R42") (pin "2") (pinfunction "2_2") (pintype "passive"))
    )
    (net (code "37") (name "Net-(IC5-Pad15)") (class "Default")
      (node (ref "IC5") (pin "15") (pinfunction "15_15") (pintype "output"))
      (node (ref "R15") (pin "1") (pinfunction "1_1") (pintype "passive"))
      (node (ref "R36") (pin "1") (pinfunction "1_1") (pintype "passive"))
    )
    (net (code "38") (name "Net-(IC5-Pad17)") (class "Default")
      (node (ref "IC5") (pin "17") (pinfunction "17_17") (pintype "input"))
      (node (ref "R30") (pin "1") (pinfunction "1_1") (pintype "passive"))
      (node (ref "R36") (pin "2") (pinfunction "2_2") (pintype "passive"))
      (node (ref "R37") (pin "1") (pinfunction "1_1") (pintype "passive"))
    )
    (net (code "39") (name "Net-(IC5-Pad18)") (class "Default")
      (node (ref "IC5") (pin "18") (pinfunction "18_18") (pintype "input"))
      (node (ref "R14") (pin "2") (pinfunction "2_2") (pintype "passive"))
      (node (ref "R15") (pin "2") (pinfunction "2_2") (pintype "passive"))
      (node (ref "R33") (pin "1") (pinfunction "1_1") (pintype "passive"))
    )
    (net (code "40") (name "Net-(IC7A--IN)") (class "Default")
      (node (ref "IC7") (pin "1") (pinfunction "OUT_1") (pintype "output"))
      (node (ref "IC7") (pin "2") (pinfunction "-IN_2") (pintype "input"))
      (node (ref "R57") (pin "1") (pinfunction "1_1") (pintype "passive"))
    )
    (net (code "41") (name "Net-(IC7B--IN)") (class "Default")
      (node (ref "IC7") (pin "6") (pinfunction "-IN_6") (pintype "input"))
      (node (ref "IC7") (pin "7") (pinfunction "OUT_7") (pintype "output"))
      (node (ref "R34") (pin "1") (pinfunction "1_1") (pintype "passive"))
    )
    (net (code "42") (name "Net-(IC9B--IN)") (class "Default")
      (node (ref "IC9") (pin "6") (pinfunction "-IN_6") (pintype "input"))
      (node (ref "R5") (pin "2") (pinfunction "2_2") (pintype "passive"))
      (node (ref "R55") (pin "1") (pinfunction "1_1") (pintype "passive"))
      (node (ref "R56") (pin "1") (pinfunction "1_1") (pintype "passive"))
      (node (ref "R62") (pin "1") (pinfunction "1_1") (pintype "passive"))
    )
    (net (code "43") (name "Net-(IC9D--IN)") (class "Default")
      (node (ref "IC9") (pin "13") (pinfunction "-IN_13") (pintype "input"))
      (node (ref "IC9") (pin "14") (pinfunction "OUT_14") (pintype "output"))
      (node (ref "R79") (pin "2") (pinfunction "2_2") (pintype "passive"))
    )
    (net (code "44") (name "Net-(IN1LEVEL-2)") (class "Default")
      (node (ref "IN1LEVEL") (pin "P$2") (pinfunction "2_P$2") (pintype "passive"))
      (node (ref "R55") (pin "2") (pinfunction "2_2") (pintype "passive"))
    )
    (net (code "45") (name "Net-(IN1LEVEL-3)") (class "Default")
      (node (ref "IN1") (pin "TIP") (pinfunction "TIP_TIP") (pintype "passive"))
      (node (ref "IN1LEVEL") (pin "P$3") (pinfunction "3_P$3") (pintype "passive"))
    )
    (net (code "46") (name "Net-(IN2LEVEL-2)") (class "Default")
      (node (ref "IN2LEVEL") (pin "P$2") (pinfunction "2_P$2") (pintype "passive"))
      (node (ref "R56") (pin "2") (pinfunction "2_2") (pintype "passive"))
    )
    (net (code "47") (name "Net-(IN2LEVEL-3)") (class "Default")
      (node (ref "IN2") (pin "TIP") (pinfunction "TIP_TIP") (pintype "passive"))
      (node (ref "IN2LEVEL") (pin "P$3") (pinfunction "3_P$3") (pintype "passive"))
    )
    (net (code "48") (name "Net-(IN3LEVEL-2)") (class "Default")
      (node (ref "IN3LEVEL") (pin "P$2") (pinfunction "2_P$2") (pintype "passive"))
      (node (ref "R62") (pin "2") (pinfunction "2_2") (pintype "passive"))
    )
    (net (code "49") (name "Net-(IN3LEVEL-3)") (class "Default")
      (node (ref "IN3") (pin "TIP") (pinfunction "TIP_TIP") (pintype "passive"))
      (node (ref "IN3LEVEL") (pin "P$3") (pinfunction "3_P$3") (pintype "passive"))
    )
    (net (code "50") (name "Net-(IN_GAIN-3)") (class "Default")
      (node (ref "IN_GAIN") (pin "P$3") (pinfunction "3_P$3") (pintype "passive"))
      (node (ref "R5") (pin "1") (pinfunction "1_1") (pintype "passive"))
    )
    (net (code "51") (name "Net-(IN_MIX-3)") (class "Default")
      (node (ref "IN_MIX") (pin "P3") (pinfunction "3_P3") (pintype "passive"))
      (node (ref "R79") (pin "1") (pinfunction "1_1") (pintype "passive"))
    )
    (net (code "52") (name "Net-(LED1A-A)") (class "Default")
      (node (ref "LED1") (pin "2") (pinfunction "A_2") (pintype "passive"))
      (node (ref "LED1") (pin "3") (pinfunction "C_3") (pintype "passive"))
      (node (ref "R1") (pin "1") (pinfunction "1_1") (pintype "passive"))
    )
    (net (code "53") (name "Net-(LED2A-A)") (class "Default")
      (node (ref "LED2") (pin "2") (pinfunction "A_2") (pintype "passive"))
      (node (ref "LED2") (pin "3") (pinfunction "C_3") (pintype "passive"))
      (node (ref "R4") (pin "1") (pinfunction "1_1") (pintype "passive"))
    )
    (net (code "54") (name "Net-(OUTPUT-3)") (class "Default")
      (node (ref "OUTPUT") (pin "P3") (pinfunction "3_P3") (pintype "passive"))
      (node (ref "R34") (pin "2") (pinfunction "2_2") (pintype "passive"))
    )
    (net (code "55") (name "Net-(OUTPUT1-3)") (class "Default")
      (node (ref "OUTPUT1") (pin "P3") (pinfunction "3_P3") (pintype "passive"))
      (node (ref "R57") (pin "2") (pinfunction "2_2") (pintype "passive"))
    )
    (net (code "56") (name "Net-(R1-F2-S)") (class "Default")
      (node (ref "R1-F2") (pin "P$2") (pinfunction "S_P$2") (pintype "passive"))
      (node (ref "R2") (pin "1") (pinfunction "1_1") (pintype "passive"))
    )
    (net (code "57") (name "Net-(R5-F1-S)") (class "Default")
      (node (ref "R5-F1") (pin "P$2") (pinfunction "S_P$2") (pintype "passive"))
      (node (ref "R6") (pin "1") (pinfunction "1_1") (pintype "passive"))
    )
    (net (code "58") (name "Net-(R9-E)") (class "Default")
      (node (ref "R10") (pin "1") (pinfunction "1_1") (pintype "passive"))
      (node (ref "R9") (pin "1") (pinfunction "E_1") (pintype "passive"))
      (node (ref "R9") (pin "2") (pinfunction "S_2") (pintype "passive"))
    )
    (net (code "59") (name "Net-(R60-E)") (class "Default")
      (node (ref "R3") (pin "1") (pinfunction "1_1") (pintype "passive"))
      (node (ref "R60") (pin "1") (pinfunction "E_1") (pintype "passive"))
      (node (ref "R60") (pin "2") (pinfunction "S_2") (pintype "passive"))
    )
    (net (code "60") (name "Net-(RES-1-2)") (class "Default")
      (node (ref "R69") (pin "1") (pinfunction "1_1") (pintype "passive"))
      (node (ref "RES-1") (pin "P2") (pinfunction "2_P2") (pintype "passive"))
    )
    (net (code "61") (name "Net-(RES-1-3)") (class "Default")
      (node (ref "D4") (pin "A") (pinfunction "A_A") (pintype "passive"))
      (node (ref "RES-1") (pin "P3") (pinfunction "3_P3") (pintype "passive"))
    )
    (net (code "62") (name "Net-(RES-2-2)") (class "Default")
      (node (ref "R71") (pin "1") (pinfunction "1_1") (pintype "passive"))
      (node (ref "RES-2") (pin "P2") (pinfunction "2_P2") (pintype "passive"))
    )
    (net (code "63") (name "Net-(RES-2-3)") (class "Default")
      (node (ref "D3") (pin "A") (pinfunction "A_A") (pintype "passive"))
      (node (ref "RES-2") (pin "P3") (pinfunction "3_P3") (pintype "passive"))
    )
    (net (code "64") (name "Net-(V-OCT-3)") (class "Default")
      (node (ref "R8") (pin "1") (pinfunction "1_1") (pintype "passive"))
      (node (ref "V-OCT") (pin "P3") (pinfunction "3_P3") (pintype "passive"))
    )
    (net (code "65") (name "Net-(V-OCT1-3)") (class "Default")
      (node (ref "R59") (pin "1") (pinfunction "1_1") (pintype "passive"))
      (node (ref "V-OCT1") (pin "P3") (pinfunction "3_P3") (pintype "passive"))
    )
    (net (code "66") (name "RESONANCE_CTL1") (class "Default")
      (node (ref "R4-RES1") (pin "P$2") (pinfunction "S_P$2") (pintype "passive"))
    )
    (net (code "67") (name "RESONANCE_CTL2") (class "Default")
      (node (ref "R39") (pin "2") (pinfunction "2_2") (pintype "passive"))
      (node (ref "R55-RES2") (pin "P$2") (pinfunction "S_P$2") (pintype "passive"))
    )
    (net (code "68") (name "RESONANCE_IN1") (class "Default")
      (node (ref "IC9") (pin "1") (pinfunction "OUT_1") (pintype "output"))
      (node (ref "IC9") (pin "2") (pinfunction "-IN_2") (pintype "input"))
      (node (ref "R4-RES1") (pin "P$1") (pinfunction "E_P$1") (pintype "passive"))
    )
    (net (code "69") (name "RESONANCE_IN2") (class "Default")
      (node (ref "IC9") (pin "8") (pinfunction "OUT_8") (pintype "output"))
      (node (ref "IC9") (pin "9") (pinfunction "-IN_9") (pintype "input"))
      (node (ref "R55-RES2") (pin "P$1") (pinfunction "E_P$1") (pintype "passive"))
    )
    (net (code "70") (name "unconnected-(IN1-SWITCH-PadNORM)") (class "Default")
      (node (ref "IN1") (pin "NORM") (pinfunction "SWITCH_NORM") (pintype "passive"))
    )
    (net (code "71") (name "unconnected-(IN2-SWITCH-PadNORM)") (class "Default")
      (node (ref "IN2") (pin "NORM") (pinfunction "SWITCH_NORM") (pintype "passive"))
    )
    (net (code "72") (name "unconnected-(IN3-SWITCH-PadNORM)") (class "Default")
      (node (ref "IN3") (pin "NORM") (pinfunction "SWITCH_NORM") (pintype "passive"))
    )
    (net (code "73") (name "unconnected-(IN_MIX-2-PadP2)") (class "Default")
      (node (ref "IN_MIX") (pin "P2") (pinfunction "2_P2") (pintype "passive"))
    )
    (net (code "74") (name "unconnected-(OUTPUT-2-PadP2)") (class "Default")
      (node (ref "OUTPUT") (pin "P2") (pinfunction "2_P2") (pintype "passive"))
    )
    (net (code "75") (name "unconnected-(OUTPUT1-2-PadP2)") (class "Default")
      (node (ref "OUTPUT1") (pin "P2") (pinfunction "2_P2") (pintype "passive"))
    )
  )
)
